# Ring_1.net
KiCad netlist of a schematic drawn in Altium Designer
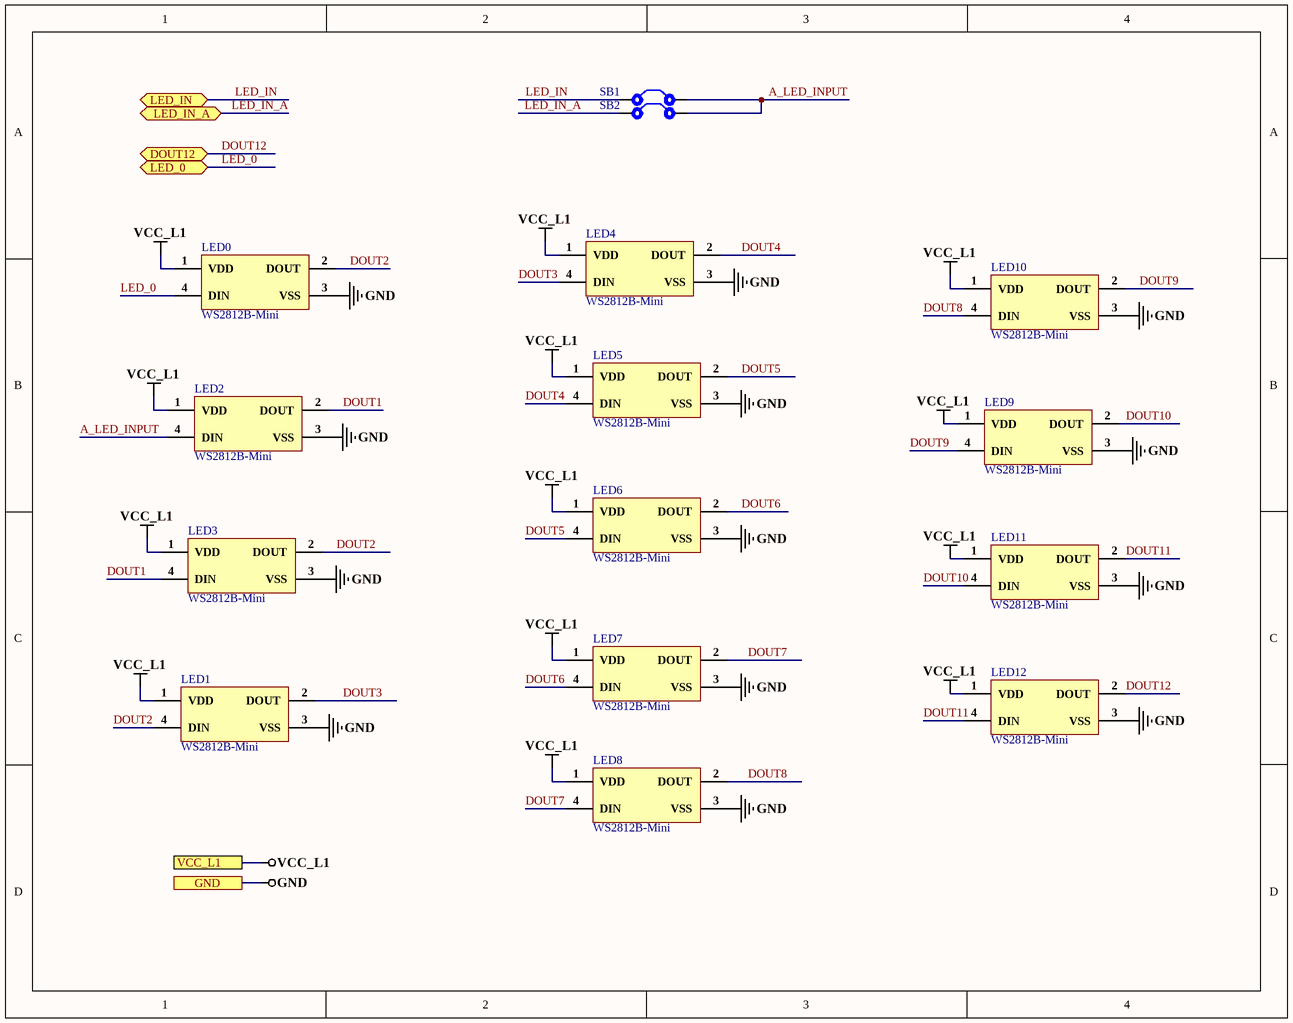
[diagram p0: Ring 1.SchDoc]

(export (version "E")
  (design (tool "Eeschema 10.0.6"))
  (components
    (comp (ref "LED0")
      (value "WS2812B-Mini")
      (footprint "WS2812B-Mini")
      (description "SMD,3.5x3.5mm Light Emitting Diodes (LED) RoHS")
      (fields (field (name "MANUFACTURER") "Worldsemi"))
      (libsource (lib "TT_IntLib") (part "WS2812B-Mini"))
    )
    (comp (ref "LED1")
      (value "WS2812B-Mini")
      (footprint "WS2812B-Mini")
      (description "SMD,3.5x3.5mm Light Emitting Diodes (LED) RoHS")
      (fields (field (name "MANUFACTURER") "Worldsemi"))
      (libsource (lib "TT_IntLib") (part "WS2812B-Mini"))
    )
    (comp (ref "LED2")
      (value "WS2812B-Mini")
      (footprint "WS2812B-Mini")
      (description "SMD,3.5x3.5mm Light Emitting Diodes (LED) RoHS")
      (fields (field (name "MANUFACTURER") "Worldsemi"))
      (libsource (lib "TT_IntLib") (part "WS2812B-Mini"))
    )
    (comp (ref "LED3")
      (value "WS2812B-Mini")
      (footprint "WS2812B-Mini")
      (description "SMD,3.5x3.5mm Light Emitting Diodes (LED) RoHS")
      (fields (field (name "MANUFACTURER") "Worldsemi"))
      (libsource (lib "TT_IntLib") (part "WS2812B-Mini"))
    )
    (comp (ref "LED4")
      (value "WS2812B-Mini")
      (footprint "WS2812B-Mini")
      (description "SMD,3.5x3.5mm Light Emitting Diodes (LED) RoHS")
      (fields (field (name "MANUFACTURER") "Worldsemi"))
      (libsource (lib "TT_IntLib") (part "WS2812B-Mini"))
    )
    (comp (ref "LED5")
      (value "WS2812B-Mini")
      (footprint "WS2812B-Mini")
      (description "SMD,3.5x3.5mm Light Emitting Diodes (LED) RoHS")
      (fields (field (name "MANUFACTURER") "Worldsemi"))
      (libsource (lib "TT_IntLib") (part "WS2812B-Mini"))
    )
    (comp (ref "LED6")
      (value "WS2812B-Mini")
      (footprint "WS2812B-Mini")
      (description "SMD,3.5x3.5mm Light Emitting Diodes (LED) RoHS")
      (fields (field (name "MANUFACTURER") "Worldsemi"))
      (libsource (lib "TT_IntLib") (part "WS2812B-Mini"))
    )
    (comp (ref "LED7")
      (value "WS2812B-Mini")
      (footprint "WS2812B-Mini")
      (description "SMD,3.5x3.5mm Light Emitting Diodes (LED) RoHS")
      (fields (field (name "MANUFACTURER") "Worldsemi"))
      (libsource (lib "TT_IntLib") (part "WS2812B-Mini"))
    )
    (comp (ref "LED8")
      (value "WS2812B-Mini")
      (footprint "WS2812B-Mini")
      (description "SMD,3.5x3.5mm Light Emitting Diodes (LED) RoHS")
      (fields (field (name "MANUFACTURER") "Worldsemi"))
      (libsource (lib "TT_IntLib") (part "WS2812B-Mini"))
    )
    (comp (ref "LED9")
      (value "WS2812B-Mini")
      (footprint "WS2812B-Mini")
      (description "SMD,3.5x3.5mm Light Emitting Diodes (LED) RoHS")
      (fields (field (name "MANUFACTURER") "Worldsemi"))
      (libsource (lib "TT_IntLib") (part "WS2812B-Mini"))
    )
    (comp (ref "LED10")
      (value "WS2812B-Mini")
      (footprint "WS2812B-Mini")
      (description "SMD,3.5x3.5mm Light Emitting Diodes (LED) RoHS")
      (fields (field (name "MANUFACTURER") "Worldsemi"))
      (libsource (lib "TT_IntLib") (part "WS2812B-Mini"))
    )
    (comp (ref "LED11")
      (value "WS2812B-Mini")
      (footprint "WS2812B-Mini")
      (description "SMD,3.5x3.5mm Light Emitting Diodes (LED) RoHS")
      (fields (field (name "MANUFACTURER") "Worldsemi"))
      (libsource (lib "TT_IntLib") (part "WS2812B-Mini"))
    )
    (comp (ref "LED12")
      (value "WS2812B-Mini")
      (footprint "WS2812B-Mini")
      (description "SMD,3.5x3.5mm Light Emitting Diodes (LED) RoHS")
      (fields (field (name "MANUFACTURER") "Worldsemi"))
      (libsource (lib "TT_IntLib") (part "WS2812B-Mini"))
    )
    (comp (ref "SB1")
      (value "Solder Bridge")
      (footprint "Solder Bridge")
      (description "Solder Bridge ON")
      (libsource (lib "TT_IntLib") (part "Solder Bridge"))
    )
    (comp (ref "SB2")
      (value "Solder Bridge")
      (footprint "Solder Bridge")
      (description "Solder Bridge ON")
      (libsource (lib "TT_IntLib") (part "Solder Bridge"))
    )
  )
  (nets
    (net (code "1") (name "/A_LED_INPUT") (class "Default")
      (node (ref "LED2") (pin "4") (pinfunction "DIN_4") (pintype "passive"))
      (node (ref "SB1") (pin "2") (pinfunction "2_2") (pintype "passive"))
      (node (ref "SB2") (pin "2") (pinfunction "2_2") (pintype "passive"))
    )
    (net (code "2") (name "/DOUT1") (class "Default")
      (node (ref "LED2") (pin "2") (pinfunction "DOUT_2") (pintype "passive"))
      (node (ref "LED3") (pin "4") (pinfunction "DIN_4") (pintype "passive"))
    )
    (net (code "3") (name "/DOUT2") (class "Default")
      (node (ref "LED0") (pin "2") (pinfunction "DOUT_2") (pintype "passive"))
      (node (ref "LED1") (pin "4") (pinfunction "DIN_4") (pintype "passive"))
      (node (ref "LED3") (pin "2") (pinfunction "DOUT_2") (pintype "passive"))
    )
    (net (code "4") (name "/DOUT3") (class "Default")
      (node (ref "LED1") (pin "2") (pinfunction "DOUT_2") (pintype "passive"))
      (node (ref "LED4") (pin "4") (pinfunction "DIN_4") (pintype "passive"))
    )
    (net (code "5") (name "/DOUT4") (class "Default")
      (node (ref "LED4") (pin "2") (pinfunction "DOUT_2") (pintype "passive"))
      (node (ref "LED5") (pin "4") (pinfunction "DIN_4") (pintype "passive"))
    )
    (net (code "6") (name "/DOUT5") (class "Default")
      (node (ref "LED5") (pin "2") (pinfunction "DOUT_2") (pintype "passive"))
      (node (ref "LED6") (pin "4") (pinfunction "DIN_4") (pintype "passive"))
    )
    (net (code "7") (name "/DOUT6") (class "Default")
      (node (ref "LED6") (pin "2") (pinfunction "DOUT_2") (pintype "passive"))
      (node (ref "LED7") (pin "4") (pinfunction "DIN_4") (pintype "passive"))
    )
    (net (code "8") (name "/DOUT7") (class "Default")
      (node (ref "LED7") (pin "2") (pinfunction "DOUT_2") (pintype "passive"))
      (node (ref "LED8") (pin "4") (pinfunction "DIN_4") (pintype "passive"))
    )
    (net (code "9") (name "/DOUT8") (class "Default")
      (node (ref "LED10") (pin "4") (pinfunction "DIN_4") (pintype "passive"))
      (node (ref "LED8") (pin "2") (pinfunction "DOUT_2") (pintype "passive"))
    )
    (net (code "10") (name "/DOUT9") (class "Default")
      (node (ref "LED10") (pin "2") (pinfunction "DOUT_2") (pintype "passive"))
      (node (ref "LED9") (pin "4") (pinfunction "DIN_4") (pintype "passive"))
    )
    (net (code "11") (name "/DOUT10") (class "Default")
      (node (ref "LED11") (pin "4") (pinfunction "DIN_4") (pintype "passive"))
      (node (ref "LED9") (pin "2") (pinfunction "DOUT_2") (pintype "passive"))
    )
    (net (code "12") (name "/DOUT11") (class "Default")
      (node (ref "LED11") (pin "2") (pinfunction "DOUT_2") (pintype "passive"))
      (node (ref "LED12") (pin "4") (pinfunction "DIN_4") (pintype "passive"))
    )
    (net (code "13") (name "/DOUT12") (class "Default")
      (node (ref "LED12") (pin "2") (pinfunction "DOUT_2") (pintype "passive"))
    )
    (net (code "14") (name "/LED_0") (class "Default")
      (node (ref "LED0") (pin "4") (pinfunction "DIN_4") (pintype "passive"))
    )
    (net (code "15") (name "/LED_IN") (class "Default")
      (node (ref "SB1") (pin "1") (pinfunction "1_1") (pintype "passive"))
    )
    (net (code "16") (name "/LED_IN_A") (class "Default")
      (node (ref "SB2") (pin "1") (pinfunction "1_1") (pintype "passive"))
    )
    (net (code "17") (name "GND") (class "Default")
      (node (ref "LED0") (pin "3") (pinfunction "VSS_3") (pintype "passive"))
      (node (ref "LED1") (pin "3") (pinfunction "VSS_3") (pintype "passive"))
      (node (ref "LED10") (pin "3") (pinfunction "VSS_3") (pintype "passive"))
      (node (ref "LED11") (pin "3") (pinfunction "VSS_3") (pintype "passive"))
      (node (ref "LED12") (pin "3") (pinfunction "VSS_3") (pintype "passive"))
      (node (ref "LED2") (pin "3") (pinfunction "VSS_3") (pintype "passive"))
      (node (ref "LED3") (pin "3") (pinfunction "VSS_3") (pintype "passive"))
      (node (ref "LED4") (pin "3") (pinfunction "VSS_3") (pintype "passive"))
      (node (ref "LED5") (pin "3") (pinfunction "VSS_3") (pintype "passive"))
      (node (ref "LED6") (pin "3") (pinfunction "VSS_3") (pintype "passive"))
      (node (ref "LED7") (pin "3") (pinfunction "VSS_3") (pintype "passive"))
      (node (ref "LED8") (pin "3") (pinfunction "VSS_3") (pintype "passive"))
      (node (ref "LED9") (pin "3") (pinfunction "VSS_3") (pintype "passive"))
    )
    (net (code "18") (name "VCC_L1") (class "Default")
      (node (ref "LED0") (pin "1") (pinfunction "VDD_1") (pintype "passive"))
      (node (ref "LED1") (pin "1") (pinfunction "VDD_1") (pintype "passive"))
      (node (ref "LED10") (pin "1") (pinfunction "VDD_1") (pintype "passive"))
      (node (ref "LED11") (pin "1") (pinfunction "VDD_1") (pintype "passive"))
      (node (ref "LED12") (pin "1") (pinfunction "VDD_1") (pintype "passive"))
      (node (ref "LED2") (pin "1") (pinfunction "VDD_1") (pintype "passive"))
      (node (ref "LED3") (pin "1") (pinfunction "VDD_1") (pintype "passive"))
      (node (ref "LED4") (pin "1") (pinfunction "VDD_1") (pintype "passive"))
      (node (ref "LED5") (pin "1") (pinfunction "VDD_1") (pintype "passive"))
      (node (ref "LED6") (pin "1") (pinfunction "VDD_1") (pintype "passive"))
      (node (ref "LED7") (pin "1") (pinfunction "VDD_1") (pintype "passive"))
      (node (ref "LED8") (pin "1") (pinfunction "VDD_1") (pintype "passive"))
      (node (ref "LED9") (pin "1") (pinfunction "VDD_1") (pintype "passive"))
    )
  )
)
